# hub_2025-11-01.net
KiCad netlist of a schematic drawn in EasyEDA Pro
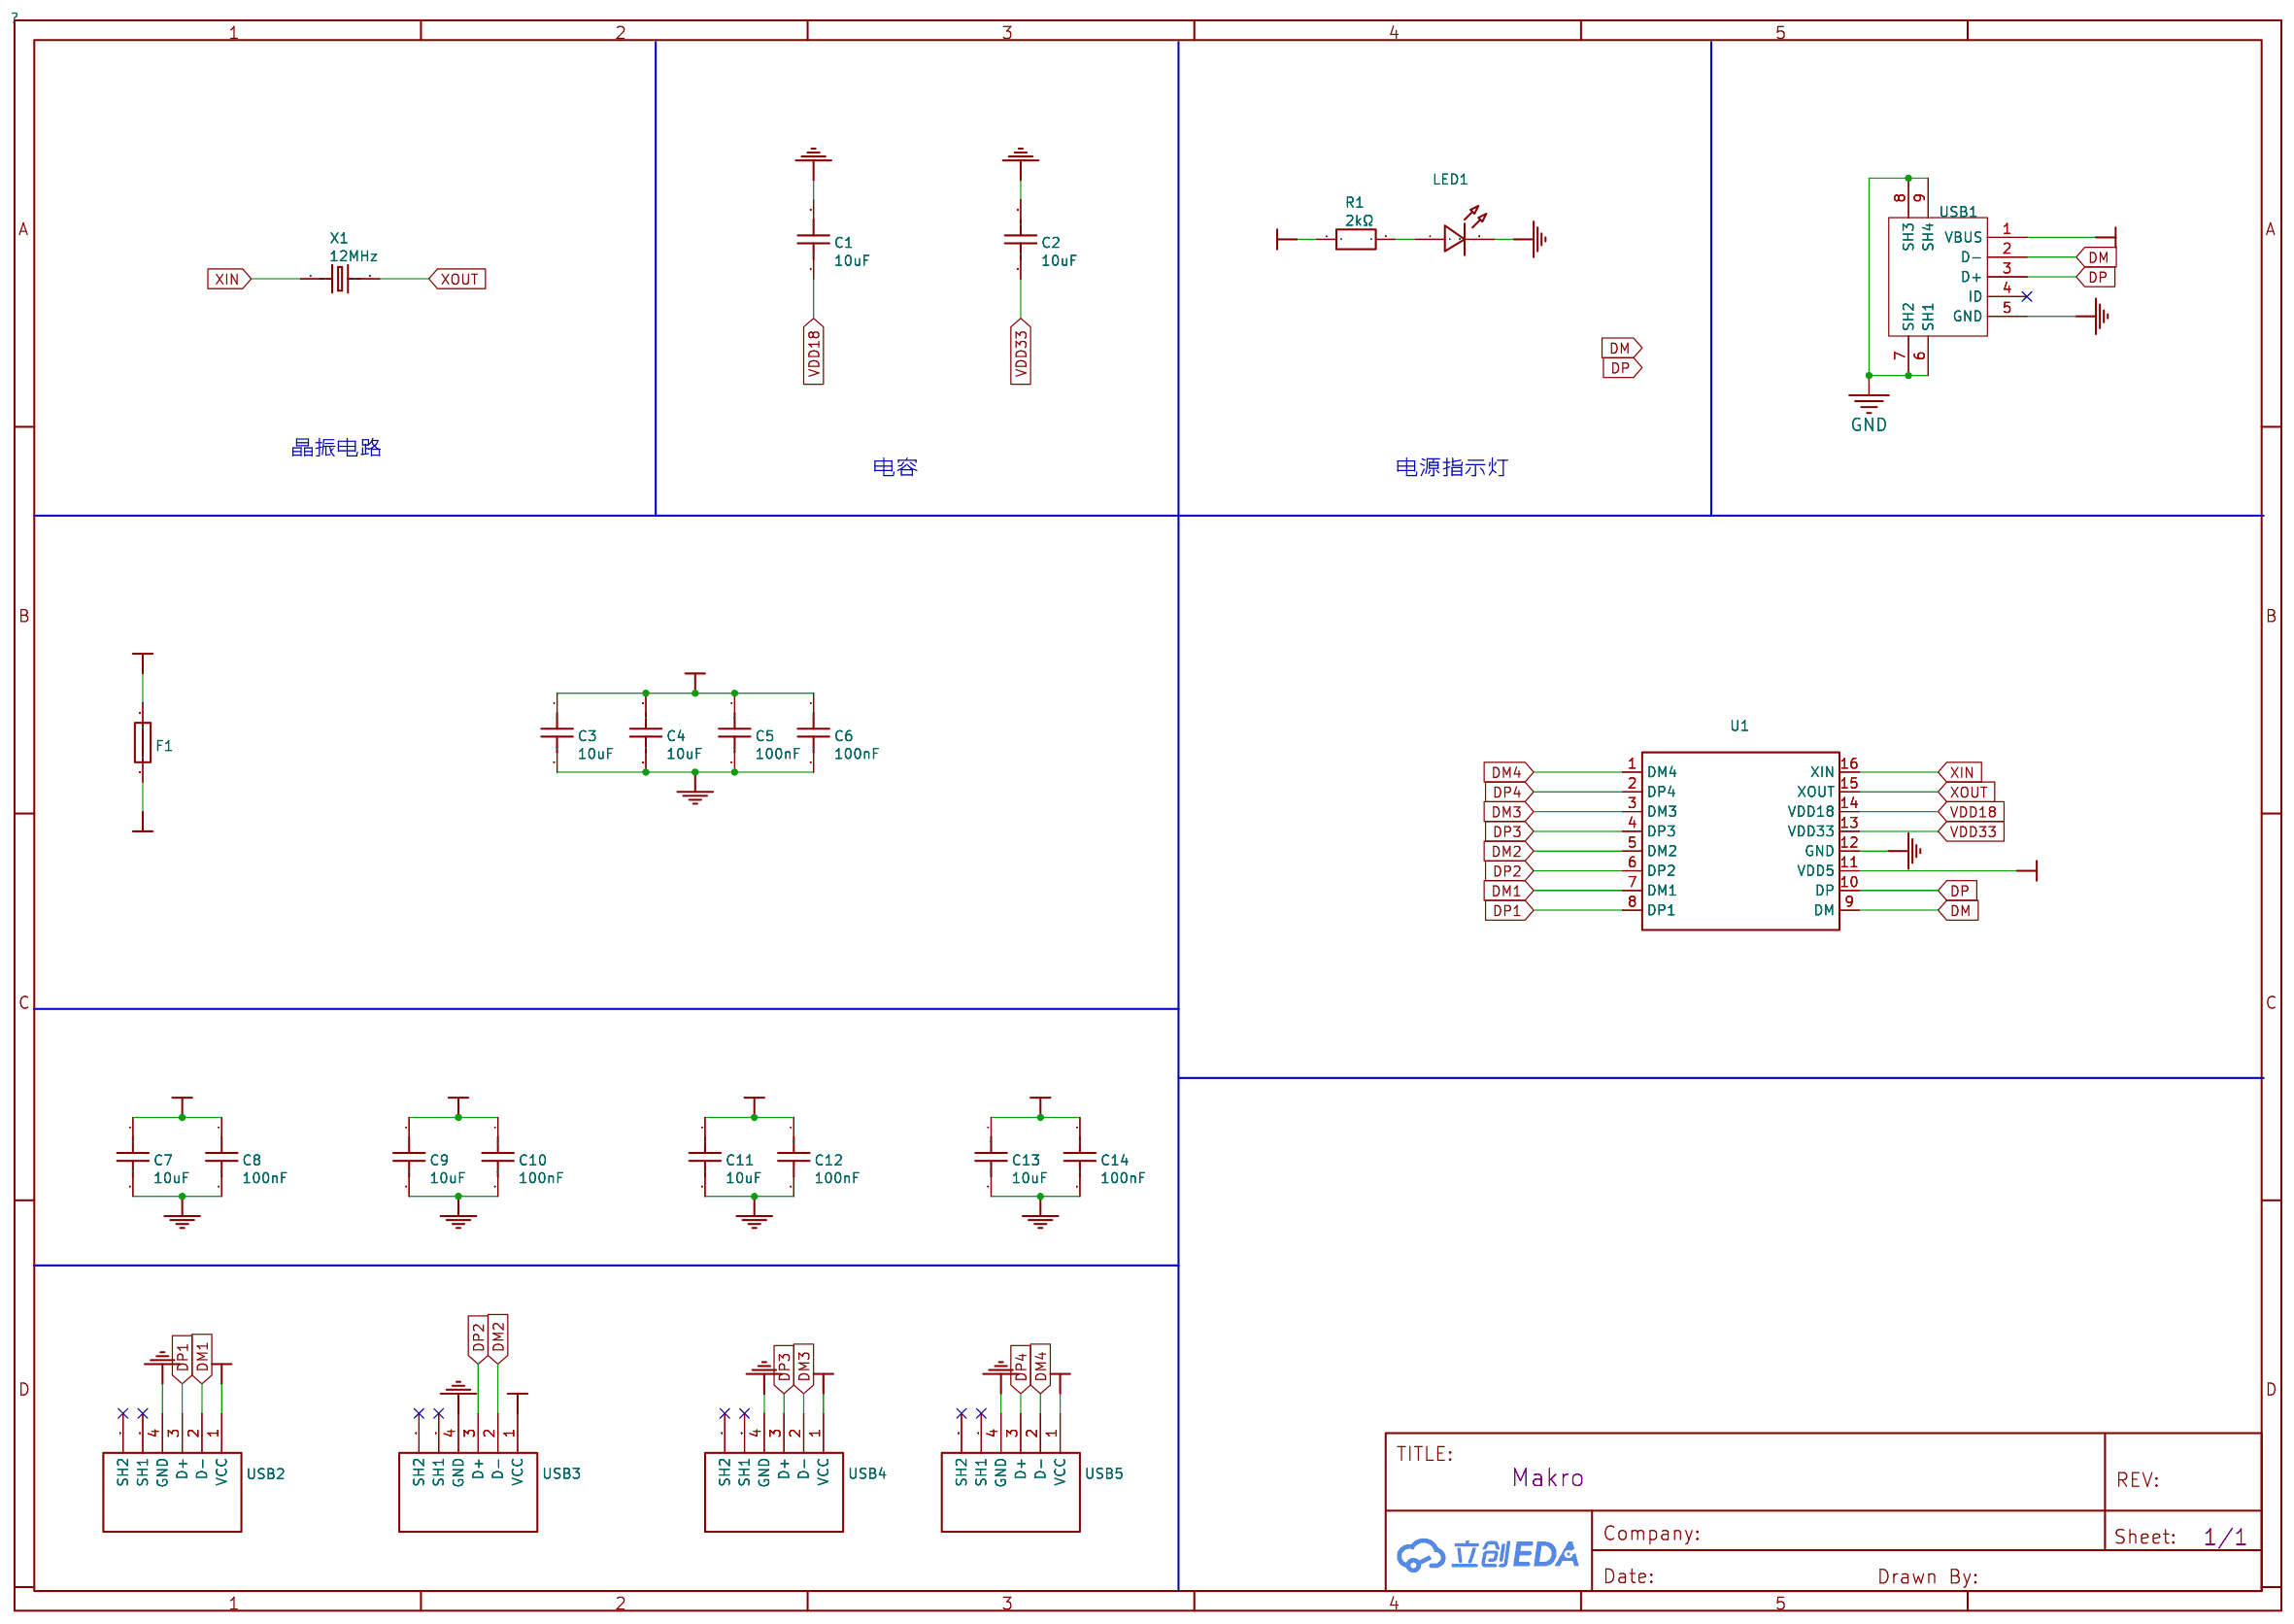
[diagram p0: schematic sheet]

(export (version "E")
  (design (tool "Eeschema 10.0.6"))
  (components
    (comp (ref "C1")
      (value "10uF")
      (description "Capacitance:10uF Tolerance:±20% Tolerance:±20% Voltage Rating:6.3V Temperature Coefficient:X5R")
      (fields (field (name "Manufacturer") "FH(风华)"))
      (libsource (lib "easyedapro") (part "10uF"))
    )
    (comp (ref "C2")
      (value "10uF")
      (description "Capacitance:10uF Tolerance:±20% Tolerance:±20% Voltage Rating:6.3V Temperature Coefficient:X5R")
      (fields (field (name "Manufacturer") "FH(风华)"))
      (libsource (lib "easyedapro") (part "10uF"))
    )
    (comp (ref "C3")
      (value "10uF")
      (description "Capacitance:10uF Tolerance:±20% Tolerance:±20% Voltage Rating:6.3V Temperature Coefficient:X5R")
      (fields (field (name "Manufacturer") "FH(风华)"))
      (libsource (lib "easyedapro") (part "10uF"))
    )
    (comp (ref "C4")
      (value "10uF")
      (description "Capacitance:10uF Tolerance:±20% Tolerance:±20% Voltage Rating:6.3V Temperature Coefficient:X5R")
      (fields (field (name "Manufacturer") "FH(风华)"))
      (libsource (lib "easyedapro") (part "10uF"))
    )
    (comp (ref "C5")
      (value "100nF")
      (description "Capacitance:100nF Tolerance:±10% Tolerance:±10% Voltage Rating:100V Temperature Coefficient:X7R")
      (fields (field (name "Manufacturer") "IHHEC(禾伸堂)"))
      (libsource (lib "easyedapro") (part "0.1uF"))
    )
    (comp (ref "C6")
      (value "100nF")
      (description "Capacitance:100nF Tolerance:±10% Tolerance:±10% Voltage Rating:100V Temperature Coefficient:X7R")
      (fields (field (name "Manufacturer") "IHHEC(禾伸堂)"))
      (libsource (lib "easyedapro") (part "0.1uF"))
    )
    (comp (ref "C7")
      (value "10uF")
      (description "Capacitance:10uF Tolerance:±20% Tolerance:±20% Voltage Rating:6.3V Temperature Coefficient:X5R")
      (fields (field (name "Manufacturer") "FH(风华)"))
      (libsource (lib "easyedapro") (part "10uF"))
    )
    (comp (ref "C8")
      (value "100nF")
      (description "Capacitance:100nF Tolerance:±10% Tolerance:±10% Voltage Rating:100V Temperature Coefficient:X7R")
      (fields (field (name "Manufacturer") "IHHEC(禾伸堂)"))
      (libsource (lib "easyedapro") (part "0.1uF"))
    )
    (comp (ref "C9")
      (value "10uF")
      (description "Capacitance:10uF Tolerance:±20% Tolerance:±20% Voltage Rating:6.3V Temperature Coefficient:X5R")
      (fields (field (name "Manufacturer") "FH(风华)"))
      (libsource (lib "easyedapro") (part "10uF"))
    )
    (comp (ref "C10")
      (value "100nF")
      (description "Capacitance:100nF Tolerance:±10% Tolerance:±10% Voltage Rating:100V Temperature Coefficient:X7R")
      (fields (field (name "Manufacturer") "IHHEC(禾伸堂)"))
      (libsource (lib "easyedapro") (part "0.1uF"))
    )
    (comp (ref "C11")
      (value "10uF")
      (description "Capacitance:10uF Tolerance:±20% Tolerance:±20% Voltage Rating:6.3V Temperature Coefficient:X5R")
      (fields (field (name "Manufacturer") "FH(风华)"))
      (libsource (lib "easyedapro") (part "10uF"))
    )
    (comp (ref "C12")
      (value "100nF")
      (description "Capacitance:100nF Tolerance:±10% Tolerance:±10% Voltage Rating:100V Temperature Coefficient:X7R")
      (fields (field (name "Manufacturer") "IHHEC(禾伸堂)"))
      (libsource (lib "easyedapro") (part "0.1uF"))
    )
    (comp (ref "C13")
      (value "10uF")
      (description "Capacitance:10uF Tolerance:±20% Tolerance:±20% Voltage Rating:6.3V Temperature Coefficient:X5R")
      (fields (field (name "Manufacturer") "FH(风华)"))
      (libsource (lib "easyedapro") (part "10uF"))
    )
    (comp (ref "C14")
      (value "100nF")
      (description "Capacitance:100nF Tolerance:±10% Tolerance:±10% Voltage Rating:100V Temperature Coefficient:X7R")
      (fields (field (name "Manufacturer") "IHHEC(禾伸堂)"))
      (libsource (lib "easyedapro") (part "0.1uF"))
    )
    (comp (ref "F1") (value "FSMD100-1206R") (libsource (lib "easyedapro") (part "FSMD100-1206R")))
    (comp (ref "LED1") (value "19-217/R6C-AL1M2VY/3T") (libsource (lib "easyedapro") (part "LED-0603_R")))
    (comp (ref "R1")
      (value "2kΩ")
      (fields (field (name "Manufacturer") "RALEC(旺诠)"))
      (libsource (lib "easyedapro") (part "2k"))
    )
    (comp (ref "U1") (value "SL2.1A") (libsource (lib "easyedapro") (part "SL2.1A")))
    (comp (ref "USB1")
      (value "MicroXNJ")
      (footprint "easyedapro:MICRO-USB-SMD_MICROXNJ")
      (fields (field (name "Manufacturer") "SHOU HAN(首韩)"))
      (libsource (lib "easyedapro") (part "MICROXNJ"))
    )
    (comp (ref "USB2") (value "U-USBAR04P-F002") (libsource (lib "easyedapro") (part "U-USBAR04P-F001")))
    (comp (ref "USB3") (value "U-USBAR04P-F002") (libsource (lib "easyedapro") (part "U-USBAR04P-F001")))
    (comp (ref "USB4") (value "U-USBAR04P-F002") (libsource (lib "easyedapro") (part "U-USBAR04P-F001")))
    (comp (ref "USB5") (value "U-USBAR04P-F002") (libsource (lib "easyedapro") (part "U-USBAR04P-F001")))
    (comp (ref "X1") (value "12MHz") (libsource (lib "easyedapro") (part "12MHz")))
  )
  (nets
    (net (code "1") (name "+5V") (class "Default")
      (node (ref "C10") (pin "1") (pinfunction "1_1") (pintype "unspecified"))
      (node (ref "C11") (pin "1") (pinfunction "1_1") (pintype "unspecified"))
      (node (ref "C12") (pin "1") (pinfunction "1_1") (pintype "unspecified"))
      (node (ref "C13") (pin "1") (pinfunction "1_1") (pintype "unspecified"))
      (node (ref "C14") (pin "1") (pinfunction "1_1") (pintype "unspecified"))
      (node (ref "C3") (pin "1") (pinfunction "1_1") (pintype "unspecified"))
      (node (ref "C4") (pin "1") (pinfunction "1_1") (pintype "unspecified"))
      (node (ref "C5") (pin "1") (pinfunction "1_1") (pintype "unspecified"))
      (node (ref "C6") (pin "1") (pinfunction "1_1") (pintype "unspecified"))
      (node (ref "C7") (pin "1") (pinfunction "1_1") (pintype "unspecified"))
      (node (ref "C8") (pin "1") (pinfunction "1_1") (pintype "unspecified"))
      (node (ref "C9") (pin "1") (pinfunction "1_1") (pintype "unspecified"))
      (node (ref "F1") (pin "1") (pinfunction "1_1") (pintype "unspecified"))
      (node (ref "R1") (pin "1") (pinfunction "1_1") (pintype "unspecified"))
      (node (ref "U1") (pin "11") (pinfunction "VDD5_11") (pintype "unspecified"))
      (node (ref "USB2") (pin "1") (pinfunction "VCC_1") (pintype "unspecified"))
      (node (ref "USB3") (pin "1") (pinfunction "VCC_1") (pintype "unspecified"))
      (node (ref "USB4") (pin "1") (pinfunction "VCC_1") (pintype "unspecified"))
      (node (ref "USB5") (pin "1") (pinfunction "VCC_1") (pintype "unspecified"))
    )
    (net (code "2") (name "DM") (class "Default")
      (node (ref "U1") (pin "9") (pinfunction "DM_9") (pintype "unspecified"))
      (node (ref "USB1") (pin "2") (pinfunction "D-_2") (pintype "unspecified"))
    )
    (net (code "3") (name "DM1") (class "Default")
      (node (ref "U1") (pin "7") (pinfunction "DM1_7") (pintype "unspecified"))
      (node (ref "USB2") (pin "2") (pinfunction "D-_2") (pintype "unspecified"))
    )
    (net (code "4") (name "DM2") (class "Default")
      (node (ref "U1") (pin "5") (pinfunction "DM2_5") (pintype "unspecified"))
      (node (ref "USB3") (pin "2") (pinfunction "D-_2") (pintype "unspecified"))
    )
    (net (code "5") (name "DM3") (class "Default")
      (node (ref "U1") (pin "3") (pinfunction "DM3_3") (pintype "unspecified"))
      (node (ref "USB4") (pin "2") (pinfunction "D-_2") (pintype "unspecified"))
    )
    (net (code "6") (name "DM4") (class "Default")
      (node (ref "U1") (pin "1") (pinfunction "DM4_1") (pintype "unspecified"))
      (node (ref "USB5") (pin "2") (pinfunction "D-_2") (pintype "unspecified"))
    )
    (net (code "7") (name "DP") (class "Default")
      (node (ref "U1") (pin "10") (pinfunction "DP_10") (pintype "unspecified"))
      (node (ref "USB1") (pin "3") (pinfunction "D+_3") (pintype "unspecified"))
    )
    (net (code "8") (name "DP1") (class "Default")
      (node (ref "U1") (pin "8") (pinfunction "DP1_8") (pintype "unspecified"))
      (node (ref "USB2") (pin "3") (pinfunction "D+_3") (pintype "unspecified"))
    )
    (net (code "9") (name "DP2") (class "Default")
      (node (ref "U1") (pin "6") (pinfunction "DP2_6") (pintype "unspecified"))
      (node (ref "USB3") (pin "3") (pinfunction "D+_3") (pintype "unspecified"))
    )
    (net (code "10") (name "DP3") (class "Default")
      (node (ref "U1") (pin "4") (pinfunction "DP3_4") (pintype "unspecified"))
      (node (ref "USB4") (pin "3") (pinfunction "D+_3") (pintype "unspecified"))
    )
    (net (code "11") (name "DP4") (class "Default")
      (node (ref "U1") (pin "2") (pinfunction "DP4_2") (pintype "unspecified"))
      (node (ref "USB5") (pin "3") (pinfunction "D+_3") (pintype "unspecified"))
    )
    (net (code "12") (name "GND") (class "Default")
      (node (ref "C1") (pin "2") (pinfunction "2_2") (pintype "unspecified"))
      (node (ref "C10") (pin "2") (pinfunction "2_2") (pintype "unspecified"))
      (node (ref "C11") (pin "2") (pinfunction "2_2") (pintype "unspecified"))
      (node (ref "C12") (pin "2") (pinfunction "2_2") (pintype "unspecified"))
      (node (ref "C13") (pin "2") (pinfunction "2_2") (pintype "unspecified"))
      (node (ref "C14") (pin "2") (pinfunction "2_2") (pintype "unspecified"))
      (node (ref "C2") (pin "2") (pinfunction "2_2") (pintype "unspecified"))
      (node (ref "C3") (pin "2") (pinfunction "2_2") (pintype "unspecified"))
      (node (ref "C4") (pin "2") (pinfunction "2_2") (pintype "unspecified"))
      (node (ref "C5") (pin "2") (pinfunction "2_2") (pintype "unspecified"))
      (node (ref "C6") (pin "2") (pinfunction "2_2") (pintype "unspecified"))
      (node (ref "C7") (pin "2") (pinfunction "2_2") (pintype "unspecified"))
      (node (ref "C8") (pin "2") (pinfunction "2_2") (pintype "unspecified"))
      (node (ref "C9") (pin "2") (pinfunction "2_2") (pintype "unspecified"))
      (node (ref "LED1") (pin "2") (pinfunction "2_2") (pintype "unspecified"))
      (node (ref "U1") (pin "12") (pinfunction "GND_12") (pintype "unspecified"))
      (node (ref "USB1") (pin "5") (pinfunction "GND_5") (pintype "unspecified"))
      (node (ref "USB1") (pin "6") (pinfunction "SH1_6") (pintype "unspecified"))
      (node (ref "USB1") (pin "7") (pinfunction "SH2_7") (pintype "unspecified"))
      (node (ref "USB1") (pin "8") (pinfunction "SH3_8") (pintype "unspecified"))
      (node (ref "USB1") (pin "9") (pinfunction "SH4_9") (pintype "unspecified"))
      (node (ref "USB2") (pin "4") (pinfunction "GND_4") (pintype "unspecified"))
      (node (ref "USB3") (pin "4") (pinfunction "GND_4") (pintype "unspecified"))
      (node (ref "USB4") (pin "4") (pinfunction "GND_4") (pintype "unspecified"))
      (node (ref "USB5") (pin "4") (pinfunction "GND_4") (pintype "unspecified"))
    )
    (net (code "13") (name "Net-(LED1-Pad1)") (class "Default")
      (node (ref "LED1") (pin "1") (pinfunction "1_1") (pintype "unspecified"))
      (node (ref "R1") (pin "2") (pinfunction "2_2") (pintype "unspecified"))
    )
    (net (code "14") (name "VBUS") (class "Default")
      (node (ref "F1") (pin "2") (pinfunction "2_2") (pintype "unspecified"))
      (node (ref "USB1") (pin "1") (pinfunction "VBUS_1") (pintype "unspecified"))
    )
    (net (code "15") (name "VDD18") (class "Default")
      (node (ref "C1") (pin "1") (pinfunction "1_1") (pintype "unspecified"))
      (node (ref "U1") (pin "14") (pinfunction "VDD18_14") (pintype "unspecified"))
    )
    (net (code "16") (name "VDD33") (class "Default")
      (node (ref "C2") (pin "1") (pinfunction "1_1") (pintype "unspecified"))
      (node (ref "U1") (pin "13") (pinfunction "VDD33_13") (pintype "unspecified"))
    )
    (net (code "17") (name "XIN") (class "Default")
      (node (ref "U1") (pin "16") (pinfunction "XIN_16") (pintype "unspecified"))
      (node (ref "X1") (pin "1") (pinfunction "1_1") (pintype "unspecified"))
    )
    (net (code "18") (name "XOUT") (class "Default")
      (node (ref "U1") (pin "15") (pinfunction "XOUT_15") (pintype "unspecified"))
      (node (ref "X1") (pin "2") (pinfunction "2_2") (pintype "unspecified"))
    )
    (net (code "19") (name "unconnected-(USB1-ID-Pad4)") (class "Default")
      (node (ref "USB1") (pin "4") (pinfunction "ID_4") (pintype "unspecified+no_connect"))
    )
    (net (code "20") (name "unconnected-(USB2-SH1-Pad5)") (class "Default")
      (node (ref "USB2") (pin "5") (pinfunction "SH1_5") (pintype "unspecified+no_connect"))
    )
    (net (code "21") (name "unconnected-(USB2-SH2-Pad6)") (class "Default")
      (node (ref "USB2") (pin "6") (pinfunction "SH2_6") (pintype "unspecified+no_connect"))
    )
    (net (code "22") (name "unconnected-(USB3-SH1-Pad5)") (class "Default")
      (node (ref "USB3") (pin "5") (pinfunction "SH1_5") (pintype "unspecified+no_connect"))
    )
    (net (code "23") (name "unconnected-(USB3-SH2-Pad6)") (class "Default")
      (node (ref "USB3") (pin "6") (pinfunction "SH2_6") (pintype "unspecified+no_connect"))
    )
    (net (code "24") (name "unconnected-(USB4-SH1-Pad5)") (class "Default")
      (node (ref "USB4") (pin "5") (pinfunction "SH1_5") (pintype "unspecified+no_connect"))
    )
    (net (code "25") (name "unconnected-(USB4-SH2-Pad6)") (class "Default")
      (node (ref "USB4") (pin "6") (pinfunction "SH2_6") (pintype "unspecified+no_connect"))
    )
    (net (code "26") (name "unconnected-(USB5-SH1-Pad5)") (class "Default")
      (node (ref "USB5") (pin "5") (pinfunction "SH1_5") (pintype "unspecified+no_connect"))
    )
    (net (code "27") (name "unconnected-(USB5-SH2-Pad6)") (class "Default")
      (node (ref "USB5") (pin "6") (pinfunction "SH2_6") (pintype "unspecified+no_connect"))
    )
  )
)
